# Charging.net
KiCad netlist of a schematic drawn in Altium Designer
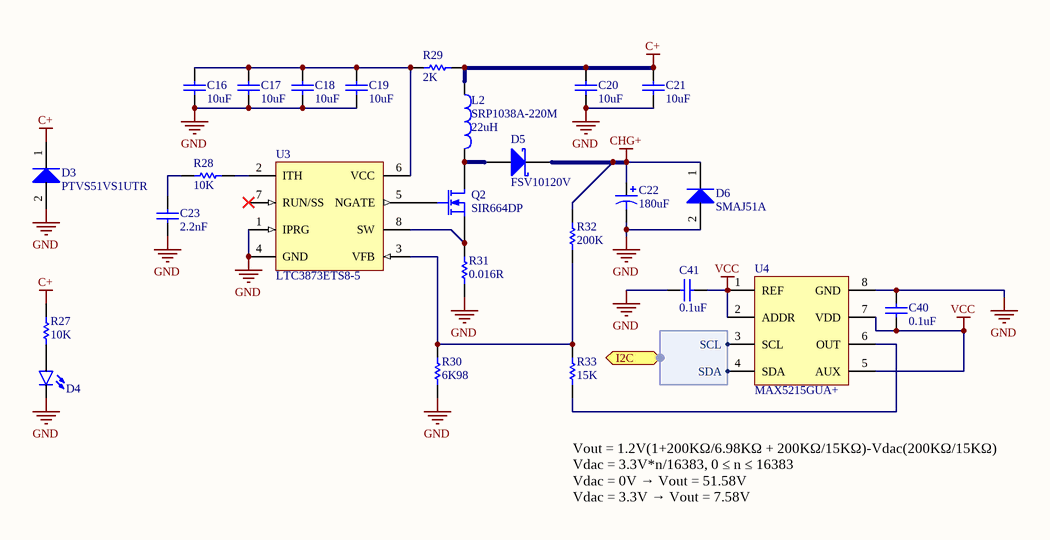
[diagram p0: Charging.SchDoc]

(export (version "E")
  (design (tool "Eeschema 10.0.6"))
  (components
    (comp (ref "C16")
      (value "10uF")
      (footprint "C0603[1608X92]")
      (description "10uF 35V 10% 0603 (1608 Metric)")
      (fields (field (name "PARTNUMBER") "GRM188R6YA106MA73D") (field (name "MANUFACTURER") "Murata"))
      (libsource (lib "Capacitors") (part "CAP_10uF_35V_0603_10%"))
    )
    (comp (ref "C17")
      (value "10uF")
      (footprint "C0603[1608X92]")
      (description "10uF 35V 10% 0603 (1608 Metric)")
      (fields (field (name "PARTNUMBER") "GRM188R6YA106MA73D") (field (name "MANUFACTURER") "Murata"))
      (libsource (lib "Capacitors") (part "CAP_10uF_35V_0603_10%"))
    )
    (comp (ref "C18")
      (value "10uF")
      (footprint "C0603[1608X92]")
      (description "10uF 35V 10% 0603 (1608 Metric)")
      (fields (field (name "PARTNUMBER") "GRM188R6YA106MA73D") (field (name "MANUFACTURER") "Murata"))
      (libsource (lib "Capacitors") (part "CAP_10uF_35V_0603_10%"))
    )
    (comp (ref "C19")
      (value "10uF")
      (footprint "C0603[1608X92]")
      (description "10uF 35V 10% 0603 (1608 Metric)")
      (fields (field (name "PARTNUMBER") "GRM188R6YA106MA73D") (field (name "MANUFACTURER") "Murata"))
      (libsource (lib "Capacitors") (part "CAP_10uF_35V_0603_10%"))
    )
    (comp (ref "C20")
      (value "10uF")
      (footprint "C1206[3216X160]")
      (description "10uF 50V 20% 1206 (3216 Metric)")
      (fields (field (name "TOLERANCE") "20%") (field (name "PARTNUMBER") "UMK316BBJ106ML-T"))
      (libsource (lib "Capacitors") (part "CAP_10uF_50V_1206_20%"))
    )
    (comp (ref "C21")
      (value "10uF")
      (footprint "C1206[3216X160]")
      (description "10uF 50V 20% 1206 (3216 Metric)")
      (fields (field (name "TOLERANCE") "20%") (field (name "PARTNUMBER") "UMK316BBJ106ML-T"))
      (libsource (lib "Capacitors") (part "CAP_10uF_50V_1206_20%"))
    )
    (comp (ref "C22")
      (value "180uF")
      (footprint "CAP-ELECTROLYTIC[10.0x12.6]")
      (description "180uF 50V 20%")
      (fields (field (name "PARTNUMBER") "PCR1H181MCL1GS") (field (name "MANUFACTURER") "Nichicon"))
      (libsource (lib "Capacitors") (part "CAP_180uF_50V_20%"))
    )
    (comp (ref "C23")
      (value "2.2nF")
      (footprint "C0402[1005X55]")
      (description "2.2nF 50V 10% 0402 (1005 Metric)")
      (fields (field (name "TOLERANCE") "10%") (field (name "PARTNUMBER") "GCM155R71H222KA37D"))
      (libsource (lib "Capacitors") (part "CAP_2.2nF_50V_0402_10%"))
    )
    (comp (ref "C40")
      (value "0.1uF")
      (footprint "C0402[1005X55]")
      (description "0.1uF 6.3V 10% 0402 (1005 Metric)")
      (fields (field (name "PARTNUMBER") "GRM155R70J104KA01D") (field (name "MANUFACTURER") "Murata"))
      (libsource (lib "Capacitors") (part "CAP_0.1uF_6.3V_0402_10%"))
    )
    (comp (ref "C41")
      (value "0.1uF")
      (footprint "C0402[1005X55]")
      (description "0.1uF 6.3V 10% 0402 (1005 Metric)")
      (fields (field (name "PARTNUMBER") "GRM155R70J104KA01D") (field (name "MANUFACTURER") "Murata"))
      (libsource (lib "Capacitors") (part "CAP_0.1uF_6.3V_0402_10%"))
    )
    (comp (ref "D3")
      (value "PTVS51VS1UTR")
      (footprint "SOD-123W")
      (fields (field (name "PARTNUMBER") "PTVS51VS1UTR,115") (field (name "MANUFACTURER") "NXP"))
      (libsource (lib "Diodes") (part "PTVS51VS1UTR,115"))
    )
    (comp (ref "D4")
      (value "LED_0603_GREEN_5mA")
      (footprint "LED0603")
      (fields (field (name "PARTNUMBER") "LTST-C193TGKT-5A") (field (name "MANUFACTURER") "Lite-On Inc."))
      (libsource (lib "LEDs") (part "LED_0603_GREEN_5mA"))
    )
    (comp (ref "D5")
      (value "FSV10120V")
      (footprint "TO-277")
      (description "Schottky Diodes & Rectifiers 10 Amp 120V Schottky Rectifier")
      (fields (field (name "MANUFACTURER") "Fairchild Semiconductor"))
      (libsource (lib "Diodes") (part "FSV10120V"))
    )
    (comp (ref "D6")
      (value "SMAJ51A")
      (footprint "DO-214AC")
      (fields (field (name "PARTNUMBER") "SMAJ51A-E3/61") (field (name "MANUFACTURER") "Vishay"))
      (libsource (lib "Diodes") (part "SMAJ51A-E3/61"))
    )
    (comp (ref "L2")
      (value "SRP1038A-220M")
      (footprint "SRP1038A")
      (description "22uH 20% 7A 1038")
      (fields (field (name "ALTIUM_VALUE") "22uH") (field (name "MANUFACTURER") "Bourns"))
      (libsource (lib "Inductors") (part "SRP1038A-220M"))
    )
    (comp (ref "Q2")
      (value "SIR664DP")
      (footprint "PowerPak-8")
      (description "N-Channel MOSFET")
      (fields (field (name "PARTNUMBER") "SIR664DP-T1-GE3") (field (name "MANUFACTURER") "Vishay"))
      (libsource (lib "MOSFETs") (part "SIR664DP-T1-GE3"))
    )
    (comp (ref "R27")
      (value "10K")
      (footprint "R0603[1608]")
      (description "10K 0.25W 1% 0603 (1005 Metric)")
      (fields (field (name "POWER") "0.25W") (field (name "TOLERANCE") "1%"))
      (libsource (lib "Resistors") (part "RES_10K_0603_1%"))
    )
    (comp (ref "R28")
      (value "10K")
      (footprint "R0402[1005]")
      (description "10K 0.063W 1% 0402 (1005 Metric)")
      (fields (field (name "TOLERANCE") "1%") (field (name "POWER") "0.063W"))
      (libsource (lib "Resistors") (part "RES_10K_0402_1%"))
    )
    (comp (ref "R29")
      (value "2K")
      (footprint "R0603[1608]")
      (description "2K 1.5W 2% 0603 (1005 Metric)")
      (fields (field (name "MANUFACTURER") "Vishay") (field (name "PARTNUMBER") "RCP0603W2K00GEB"))
      (libsource (lib "Resistors") (part "RES_2K_0603_2%"))
    )
    (comp (ref "R30")
      (value "6K98")
      (footprint "R0402[1005]")
      (description "6K98 0.063W 1% 0402 (1005 Metric)")
      (fields (field (name "POWER") "0.063W") (field (name "TOLERANCE") "1%"))
      (libsource (lib "Resistors") (part "RES_6K98_0402_1%"))
    )
    (comp (ref "R31")
      (value "0.016R")
      (footprint "R1206[3216]")
      (description "0.016R 1W 1% 1206 (3216 Metric)")
      (fields (field (name "POWER") "1W") (field (name "TOLERANCE") "1%"))
      (libsource (lib "Resistors") (part "RES_0.016R_1206_1%"))
    )
    (comp (ref "R32")
      (value "200K")
      (footprint "R0402[1005]")
      (description "200K 0.063W 1% 0402 (1005 Metric)")
      (fields (field (name "POWER") "0.063W") (field (name "TOLERANCE") "1%"))
      (libsource (lib "Resistors") (part "RES_200K_0402_1%"))
    )
    (comp (ref "R33")
      (value "15K")
      (footprint "R0402[1005]")
      (description "15K 0.063W 1% 0402 (1005 Metric)")
      (fields (field (name "MANUFACTURER") "KOA Speer") (field (name "PARTNUMBER") "RK73H1ETTP1502F"))
      (libsource (lib "Resistors") (part "RES_15K_0402_1%"))
    )
    (comp (ref "U3")
      (value "LTC3873ETS8-5")
      (footprint "SOT-23-8")
      (fields
        (field (name "PARTNUMBER") "LTC3873ETS8-5#PBF")
        (field (name "MANUFACTURER") "Linear Technology")
      )
      (libsource (lib "ICs") (part "LTC3873ETS8"))
    )
    (comp (ref "U4")
      (value "MAX5215GUA+")
      (footprint "MSOP-8")
      (description "14 Bit Digital to Analog Converter")
      (fields (field (name "MANUFACTURER") "Maxim Integrated"))
      (libsource (lib "ICs") (part "MAX5215GUA+"))
    )
  )
  (nets
    (net (code "2") (name "/SCL") (class "Default")
      (node (ref "U4") (pin "3") (pinfunction "SCL_3") (pintype "passive"))
    )
    (net (code "3") (name "/SDA") (class "Default")
      (node (ref "U4") (pin "4") (pinfunction "SDA_4") (pintype "passive"))
    )
    (net (code "5") (name "C+") (class "Default")
      (node (ref "C20") (pin "2") (pinfunction "2_2") (pintype "passive"))
      (node (ref "C21") (pin "2") (pinfunction "2_2") (pintype "passive"))
      (node (ref "D3") (pin "1") (pinfunction "K_1") (pintype "passive"))
      (node (ref "L2") (pin "1") (pinfunction "1_1") (pintype "passive"))
      (node (ref "R27") (pin "2") (pinfunction "2_2") (pintype "passive"))
      (node (ref "R29") (pin "2") (pinfunction "2_2") (pintype "passive"))
    )
    (net (code "6") (name "CHG+") (class "Default")
      (node (ref "C22") (pin "1") (pinfunction "1_1") (pintype "passive"))
      (node (ref "D5") (pin "1") (pinfunction "K_1") (pintype "passive"))
      (node (ref "D6") (pin "1") (pinfunction "K_1") (pintype "passive"))
      (node (ref "R32") (pin "2") (pinfunction "2_2") (pintype "passive"))
    )
    (net (code "7") (name "GND") (class "Default")
      (node (ref "C16") (pin "1") (pinfunction "1_1") (pintype "passive"))
      (node (ref "C17") (pin "1") (pinfunction "1_1") (pintype "passive"))
      (node (ref "C18") (pin "1") (pinfunction "1_1") (pintype "passive"))
      (node (ref "C19") (pin "1") (pinfunction "1_1") (pintype "passive"))
      (node (ref "C20") (pin "1") (pinfunction "1_1") (pintype "passive"))
      (node (ref "C21") (pin "1") (pinfunction "1_1") (pintype "passive"))
      (node (ref "C22") (pin "2") (pinfunction "2_2") (pintype "passive"))
      (node (ref "C23") (pin "1") (pinfunction "1_1") (pintype "passive"))
      (node (ref "C40") (pin "1") (pinfunction "1_1") (pintype "passive"))
      (node (ref "C41") (pin "1") (pinfunction "1_1") (pintype "passive"))
      (node (ref "D3") (pin "2") (pinfunction "A_2") (pintype "passive"))
      (node (ref "D4") (pin "C") (pinfunction "C_C") (pintype "passive"))
      (node (ref "D6") (pin "2") (pinfunction "A_2") (pintype "passive"))
      (node (ref "R30") (pin "1") (pinfunction "1_1") (pintype "passive"))
      (node (ref "R31") (pin "1") (pinfunction "1_1") (pintype "passive"))
      (node (ref "U3") (pin "1") (pinfunction "IPRG_1") (pintype "input"))
      (node (ref "U3") (pin "4") (pinfunction "GND_4") (pintype "power_in"))
      (node (ref "U4") (pin "8") (pinfunction "GND_8") (pintype "power_in"))
    )
    (net (code "8") (name "Net-(C23-Pad2)") (class "Default")
      (node (ref "C23") (pin "2") (pinfunction "2_2") (pintype "passive"))
      (node (ref "R28") (pin "2") (pinfunction "2_2") (pintype "passive"))
    )
    (net (code "9") (name "Net-(D4-PadA)") (class "Default")
      (node (ref "D4") (pin "A") (pinfunction "A_A") (pintype "passive"))
      (node (ref "R27") (pin "1") (pinfunction "1_1") (pintype "passive"))
    )
    (net (code "10") (name "Net-(D5-A)") (class "Default")
      (node (ref "D5") (pin "2") (pinfunction "A_2") (pintype "passive"))
      (node (ref "L2") (pin "2") (pinfunction "2_2") (pintype "passive"))
      (node (ref "Q2") (pin "3") (pinfunction "D_3") (pintype "passive"))
    )
    (net (code "11") (name "Net-(Q2-G)") (class "Default")
      (node (ref "Q2") (pin "2") (pinfunction "G_2") (pintype "passive"))
      (node (ref "U3") (pin "5") (pinfunction "NGATE_5") (pintype "output"))
    )
    (net (code "12") (name "Net-(Q2-S)") (class "Default")
      (node (ref "Q2") (pin "1") (pinfunction "S_1") (pintype "passive"))
      (node (ref "R31") (pin "2") (pinfunction "2_2") (pintype "passive"))
      (node (ref "U3") (pin "8") (pinfunction "SW_8") (pintype "passive"))
    )
    (net (code "13") (name "Net-(U3-ITH)") (class "Default")
      (node (ref "R28") (pin "1") (pinfunction "1_1") (pintype "passive"))
      (node (ref "U3") (pin "2") (pinfunction "ITH_2") (pintype "passive"))
    )
    (net (code "14") (name "Net-(U3-VCC)") (class "Default")
      (node (ref "C16") (pin "2") (pinfunction "2_2") (pintype "passive"))
      (node (ref "C17") (pin "2") (pinfunction "2_2") (pintype "passive"))
      (node (ref "C18") (pin "2") (pinfunction "2_2") (pintype "passive"))
      (node (ref "C19") (pin "2") (pinfunction "2_2") (pintype "passive"))
      (node (ref "R29") (pin "1") (pinfunction "1_1") (pintype "passive"))
      (node (ref "U3") (pin "6") (pinfunction "VCC_6") (pintype "power_in"))
    )
    (net (code "15") (name "Net-(U3-VFB)") (class "Default")
      (node (ref "R30") (pin "2") (pinfunction "2_2") (pintype "passive"))
      (node (ref "R32") (pin "1") (pinfunction "1_1") (pintype "passive"))
      (node (ref "R33") (pin "2") (pinfunction "2_2") (pintype "passive"))
      (node (ref "U3") (pin "3") (pinfunction "VFB_3") (pintype "input"))
    )
    (net (code "16") (name "Net-(U4-OUT)") (class "Default")
      (node (ref "R33") (pin "1") (pinfunction "1_1") (pintype "passive"))
      (node (ref "U4") (pin "6") (pinfunction "OUT_6") (pintype "passive"))
    )
    (net (code "17") (name "VCC") (class "Default")
      (node (ref "C40") (pin "2") (pinfunction "2_2") (pintype "passive"))
      (node (ref "C41") (pin "2") (pinfunction "2_2") (pintype "passive"))
      (node (ref "U4") (pin "1") (pinfunction "REF_1") (pintype "passive"))
      (node (ref "U4") (pin "2") (pinfunction "ADDR_2") (pintype "passive"))
      (node (ref "U4") (pin "5") (pinfunction "AUX_5") (pintype "passive"))
      (node (ref "U4") (pin "7") (pinfunction "VDD_7") (pintype "power_in"))
    )
    (net (code "18") (name "unconnected-(U3-RUN{slash}SS-Pad7)") (class "Default")
      (node (ref "U3") (pin "7") (pinfunction "RUN/SS_7") (pintype "input+no_connect"))
    )
  )
)
